# voltage.net
KiCad netlist of a schematic drawn in EAGLE
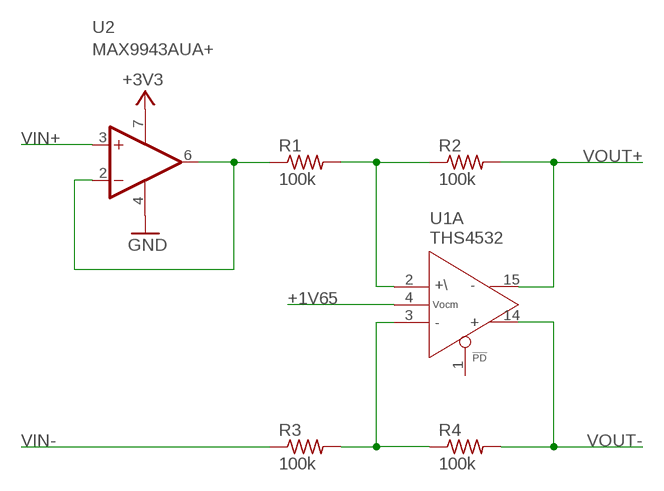
[diagram p0: schematic, sheet 1]

(export (version "E")
  (design (tool "Eeschema 10.0.6"))
  (components
    (comp (ref "R1")
      (value "100k")
      (footprint "eagle-import:R0805")
      (libsource (lib "eagle-import") (part "R-US_R0805"))
    )
    (comp (ref "R2")
      (value "100k")
      (footprint "eagle-import:R0805")
      (libsource (lib "eagle-import") (part "R-US_R0805"))
    )
    (comp (ref "R3")
      (value "100k")
      (footprint "eagle-import:R0805")
      (libsource (lib "eagle-import") (part "R-US_R0805"))
    )
    (comp (ref "R4")
      (value "100k")
      (footprint "eagle-import:R0805")
      (libsource (lib "eagle-import") (part "R-US_R0805"))
    )
    (comp (ref "U1")
      (value "THS4532")
      (footprint "eagle-import:SOP65P640X120-16N")
      (fields
        (field (name "MPN") "THS4532IPW")
        (field (name "SPICEPREFIX") "X")
        (field (name "AUTHOR") "John Madden <jmadden173@pm.me>")
      )
      (libsource (lib "eagle-import") (part "THS4532"))
    )
    (comp (ref "U2")
      (value "MAX9943AUA+")
      (footprint "eagle-import:SOP65P490X110-8N")
      (fields (field (name "MPN") "MAX9943AUA+T") (field (name "AUTHOR") "John Madden <jmadden173@pm.me>"))
      (libsource (lib "eagle-import") (part "MAX9943AUA+"))
    )
  )
  (nets
    (net (code "1") (name "+3V3") (class "Default")
      (node (ref "U2") (pin "7") (pinfunction "V+_7") (pintype "power_in"))
    )
    (net (code "2") (name "/+1V65") (class "Default")
      (node (ref "U1") (pin "4") (pinfunction "VOCM_4") (pintype "input"))
    )
    (net (code "3") (name "/VIN+") (class "Default")
      (node (ref "U2") (pin "3") (pinfunction "+IN_3") (pintype "input"))
    )
    (net (code "4") (name "/VIN-") (class "Default")
      (node (ref "R3") (pin "1") (pinfunction "1_1") (pintype "passive"))
    )
    (net (code "5") (name "/VOUT+") (class "Default")
      (node (ref "R2") (pin "2") (pinfunction "2_2") (pintype "passive"))
      (node (ref "U1") (pin "15") (pinfunction "OUT-_15") (pintype "output"))
    )
    (net (code "6") (name "/VOUT-") (class "Default")
      (node (ref "R4") (pin "2") (pinfunction "2_2") (pintype "passive"))
      (node (ref "U1") (pin "14") (pinfunction "OUT+_14") (pintype "output"))
    )
    (net (code "7") (name "GND") (class "Default")
      (node (ref "U2") (pin "4") (pinfunction "V-_4") (pintype "power_in"))
    )
    (net (code "8") (name "Net-(U1A-+IN)") (class "Default")
      (node (ref "R1") (pin "2") (pinfunction "2_2") (pintype "passive"))
      (node (ref "R2") (pin "1") (pinfunction "1_1") (pintype "passive"))
      (node (ref "U1") (pin "2") (pinfunction "+IN_2") (pintype "input"))
    )
    (net (code "9") (name "Net-(U1A--IN)") (class "Default")
      (node (ref "R3") (pin "2") (pinfunction "2_2") (pintype "passive"))
      (node (ref "R4") (pin "1") (pinfunction "1_1") (pintype "passive"))
      (node (ref "U1") (pin "3") (pinfunction "-IN_3") (pintype "input"))
    )
    (net (code "10") (name "Net-(U2--IN)") (class "Default")
      (node (ref "R1") (pin "1") (pinfunction "1_1") (pintype "passive"))
      (node (ref "U2") (pin "2") (pinfunction "-IN_2") (pintype "input"))
      (node (ref "U2") (pin "6") (pinfunction "OUT_6") (pintype "output"))
    )
    (net (code "11") (name "unconnected-(U1A-~{PD}-Pad1)") (class "Default")
      (node (ref "U1") (pin "1") (pinfunction "~{PD}_1") (pintype "input"))
    )
  )
)
